# Pressure_ADC.net
KiCad netlist of a schematic drawn in Altium Designer
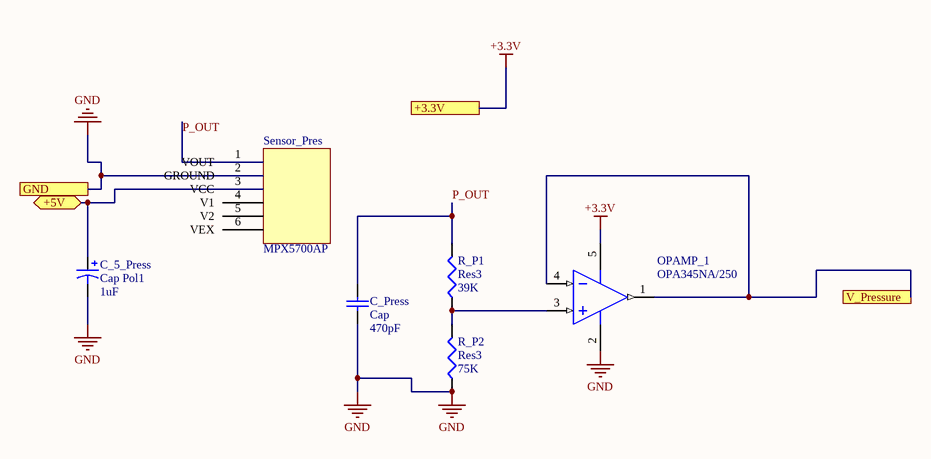
[diagram p0: Pressure ADC.SchDoc]

(export (version "E")
  (design (tool "Eeschema 10.0.6"))
  (components
    (comp (ref "C_5_Press")
      (value "Cap Pol1")
      (footprint "CAPR5-4X5")
      (description "Polarized Capacitor (Radial)")
      (fields (field (name "ALTIUM_VALUE") "1uF") (field (name "PUBLISHER") "Altium Limited"))
      (libsource (lib "Miscellaneous Devices") (part "Cap Pol1"))
    )
    (comp (ref "C_Press")
      (value "Cap")
      (footprint "J1-0603")
      (description "Capacitor")
      (fields (field (name "ALTIUM_VALUE") "470pF") (field (name "PUBLISHER") "Altium Limited"))
      (libsource (lib "Miscellaneous Devices") (part "Cap"))
    )
    (comp (ref "OPAMP_1")
      (value "OPA345NA/250")
      (footprint "TI-DBV5_N")
      (fields (field (name "MANUFACTURER") "Texas Instruments"))
      (libsource (lib "TI Amplifiers and Linear Operational Amplifier Precision Amplifier Part One") (part "OPA345NA/250"))
    )
    (comp (ref "R_P1")
      (value "Res3")
      (footprint "J1-0603")
      (description "Resistor")
      (fields (field (name "ALTIUM_VALUE") "39K") (field (name "PUBLISHER") "Altium Limited"))
      (libsource (lib "Miscellaneous Devices") (part "Res3"))
    )
    (comp (ref "R_P2")
      (value "Res3")
      (footprint "J1-0603")
      (description "Resistor")
      (fields (field (name "ALTIUM_VALUE") "75K") (field (name "PUBLISHER") "Altium Limited"))
      (libsource (lib "Miscellaneous Devices") (part "Res3"))
    )
    (comp (ref "Sensor_Pres")
      (value "MPX5700AP")
      (footprint "HDR1X6H")
      (libsource (lib "XSUB_COMP") (part "MPX5700AP"))
    )
  )
  (nets
    (net (code "1") (name "+3.3V") (class "Default")
      (node (ref "OPAMP_1") (pin "5") (pinfunction "V+_5") (pintype "power_in"))
    )
    (net (code "2") (name "/+5V") (class "Default")
      (node (ref "C_5_Press") (pin "1") (pinfunction "1_1") (pintype "passive"))
      (node (ref "Sensor_Pres") (pin "3") (pinfunction "VCC_3") (pintype "passive"))
    )
    (net (code "3") (name "/P_OUT") (class "Default")
      (node (ref "C_Press") (pin "2") (pinfunction "2_2") (pintype "passive"))
      (node (ref "R_P1") (pin "2") (pinfunction "2_2") (pintype "passive"))
      (node (ref "Sensor_Pres") (pin "1") (pinfunction "VOUT_1") (pintype "passive"))
    )
    (net (code "4") (name "/V_Pressure") (class "Default")
      (node (ref "OPAMP_1") (pin "1") (pinfunction "OUT_1") (pintype "output"))
      (node (ref "OPAMP_1") (pin "4") (pinfunction "IN-_4") (pintype "input"))
    )
    (net (code "5") (name "GND") (class "Default")
      (node (ref "C_5_Press") (pin "2") (pinfunction "2_2") (pintype "passive"))
      (node (ref "C_Press") (pin "1") (pinfunction "1_1") (pintype "passive"))
      (node (ref "OPAMP_1") (pin "2") (pinfunction "V-_2") (pintype "power_in"))
      (node (ref "R_P2") (pin "1") (pinfunction "1_1") (pintype "passive"))
      (node (ref "Sensor_Pres") (pin "2") (pinfunction "GROUND_2") (pintype "passive"))
    )
    (net (code "6") (name "Net-(OPAMP_1-IN+)") (class "Default")
      (node (ref "OPAMP_1") (pin "3") (pinfunction "IN+_3") (pintype "input"))
      (node (ref "R_P1") (pin "1") (pinfunction "1_1") (pintype "passive"))
      (node (ref "R_P2") (pin "2") (pinfunction "2_2") (pintype "passive"))
    )
    (net (code "7") (name "unconnected-(Sensor_Pres-V1-Pad4)") (class "Default")
      (node (ref "Sensor_Pres") (pin "4") (pinfunction "V1_4") (pintype "passive"))
    )
    (net (code "8") (name "unconnected-(Sensor_Pres-V2-Pad5)") (class "Default")
      (node (ref "Sensor_Pres") (pin "5") (pinfunction "V2_5") (pintype "passive"))
    )
    (net (code "9") (name "unconnected-(Sensor_Pres-VEX-Pad6)") (class "Default")
      (node (ref "Sensor_Pres") (pin "6") (pinfunction "VEX_6") (pintype "passive"))
    )
  )
)
